# RP_ComputeModule3_rev_3_0_POWER.net
KiCad netlist of a schematic drawn in Altium Designer
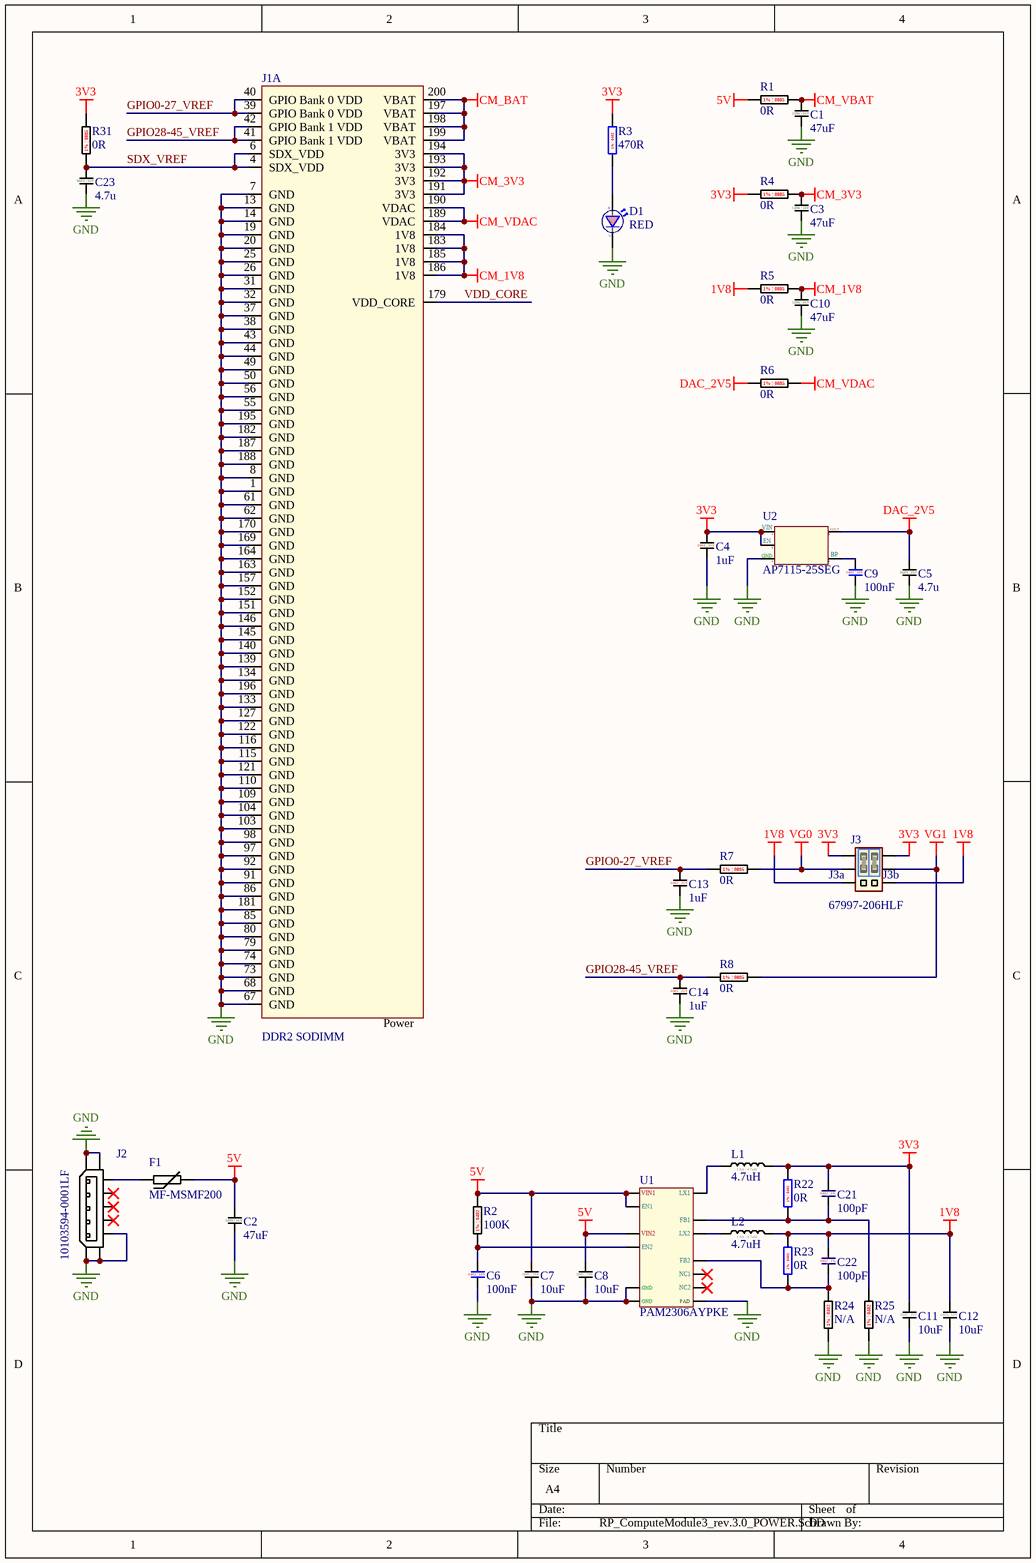
[diagram p0: RP_ComputeModule3_rev.3.0_POWER.SchDoc]

(export (version "E")
  (design (tool "Eeschema 10.0.6"))
  (components
    (comp (ref "C1")
      (value "47uF")
      (footprint "MURATA C1206 / CAPC3216X94N")
      (fields
        (field (name "MANUFACTURER") "TDK")
        (field (name "MANUFACTURER PART NUMBER") "C3216JB1C476M160AB")
        (field (name "TOLERANCE") "20%")
      )
      (libsource (lib "Murata_Capacitors") (part "C3216JB1C476M160AB"))
    )
    (comp (ref "C2")
      (value "47uF")
      (footprint "MURATA C1206 / CAPC3216X94N")
      (fields
        (field (name "MANUFACTURER") "TDK")
        (field (name "MANUFACTURER PART NUMBER") "C3216JB1C476M160AB")
        (field (name "TOLERANCE") "20%")
      )
      (libsource (lib "Murata_Capacitors") (part "C3216JB1C476M160AB"))
    )
    (comp (ref "C3")
      (value "47uF")
      (footprint "MURATA C1206 / CAPC3216X94N")
      (fields
        (field (name "MANUFACTURER") "TDK")
        (field (name "MANUFACTURER PART NUMBER") "C3216JB1C476M160AB")
        (field (name "TOLERANCE") "20%")
      )
      (libsource (lib "Murata_Capacitors") (part "C3216JB1C476M160AB"))
    )
    (comp (ref "C4")
      (value "1uF")
      (footprint "TDK 0402 C")
      (description "Multilayer Ceramic Capacitors MLCC - SMD/SMT 0402 25V 1uF X5R 10% T: 0.5mm")
      (fields
        (field (name "MANUFACTURER") "TDK")
        (field (name "MANUFACTURER PART NUMBER") "C1005X5R1E105K050BC")
      )
      (libsource (lib "TDK_Capacitors") (part "C1005X5R1E105K050BC"))
    )
    (comp (ref "C5")
      (value "4.7u")
      (footprint "0603 Murata")
      (description "4.7µF 35V Ceramic Capacitor X5R 0603 (1608 Metric) 0.063\" L x 0.031\" W (1.60mm x 0.80mm)")
      (fields
        (field (name "MANUFACTURER") "Murata")
        (field (name "MANUFACTURER PART NUMBER") "GRT188R6YA475KE13D")
      )
      (libsource (lib "Murata_Capacitors") (part "GRT188R6YA475KE13D"))
    )
    (comp (ref "C6")
      (value "100nF")
      (footprint "GJM 0402 C")
      (description "Multilayer Ceramic Capacitors MLCC - SMD/SMT 0402 0.1uF 10volts 5%")
      (fields
        (field (name "MANUFACTURER") "Murata Electronics")
        (field (name "MANUFACTURER PART NUMBER") "GRM155R71A104JA01D")
      )
      (libsource (lib "Murata_Capacitors") (part "GRM155R71A104JA01D"))
    )
    (comp (ref "C7")
      (value "10uF")
      (footprint "0805 CGA Series")
      (fields
        (field (name "MANUFACTURER") "TDK")
        (field (name "MANUFACTURER PART NUMBER") "C2012X7S1C106K125AC")
      )
      (libsource (lib "TDK_Capacitors") (part "C2012X7S1C106K125AC"))
    )
    (comp (ref "C8")
      (value "10uF")
      (footprint "0805 CGA Series")
      (fields
        (field (name "MANUFACTURER") "TDK")
        (field (name "MANUFACTURER PART NUMBER") "C2012X7S1C106K125AC")
      )
      (libsource (lib "TDK_Capacitors") (part "C2012X7S1C106K125AC"))
    )
    (comp (ref "C9")
      (value "100nF")
      (footprint "GJM 0402 C")
      (description "Multilayer Ceramic Capacitors MLCC - SMD/SMT 0402 0.1uF 10volts 5%")
      (fields
        (field (name "MANUFACTURER") "Murata Electronics")
        (field (name "MANUFACTURER PART NUMBER") "GRM155R71A104JA01D")
      )
      (libsource (lib "Murata_Capacitors") (part "GRM155R71A104JA01D"))
    )
    (comp (ref "C10")
      (value "47uF")
      (footprint "MURATA C1206 / CAPC3216X94N")
      (fields
        (field (name "MANUFACTURER") "TDK")
        (field (name "MANUFACTURER PART NUMBER") "C3216JB1C476M160AB")
        (field (name "TOLERANCE") "20%")
      )
      (libsource (lib "Murata_Capacitors") (part "C3216JB1C476M160AB"))
    )
    (comp (ref "C11")
      (value "10uF")
      (footprint "0805 CGA Series")
      (fields
        (field (name "MANUFACTURER") "TDK")
        (field (name "MANUFACTURER PART NUMBER") "C2012X7S1C106K125AC")
      )
      (libsource (lib "TDK_Capacitors") (part "C2012X7S1C106K125AC"))
    )
    (comp (ref "C12")
      (value "10uF")
      (footprint "0805 CGA Series")
      (fields
        (field (name "MANUFACTURER") "TDK")
        (field (name "MANUFACTURER PART NUMBER") "C2012X7S1C106K125AC")
      )
      (libsource (lib "TDK_Capacitors") (part "C2012X7S1C106K125AC"))
    )
    (comp (ref "C13")
      (value "1uF")
      (footprint "TDK 0402 C")
      (description "Multilayer Ceramic Capacitors MLCC - SMD/SMT 0402 25V 1uF X5R 10% T: 0.5mm")
      (fields
        (field (name "MANUFACTURER") "TDK")
        (field (name "MANUFACTURER PART NUMBER") "C1005X5R1E105K050BC")
      )
      (libsource (lib "TDK_Capacitors") (part "C1005X5R1E105K050BC"))
    )
    (comp (ref "C14")
      (value "1uF")
      (footprint "TDK 0402 C")
      (description "Multilayer Ceramic Capacitors MLCC - SMD/SMT 0402 25V 1uF X5R 10% T: 0.5mm")
      (fields
        (field (name "MANUFACTURER") "TDK")
        (field (name "MANUFACTURER PART NUMBER") "C1005X5R1E105K050BC")
      )
      (libsource (lib "TDK_Capacitors") (part "C1005X5R1E105K050BC"))
    )
    (comp (ref "C21")
      (value "100pF")
      (footprint "Cap0402 MIN Vishay N/A")
      (description "Multilayer Ceramic Capacitors MLCC - SMD/SMT 0402 100pF 50volts C0G 1%")
      (fields
        (field (name "MANUFACTURER") "Vishay Vitramon")
        (field (name "MANUFACTURER PART NUMBER") "VJ0402A101FXACW1BC")
      )
      (libsource (lib "Vishay_Library") (part "VJ0402A101FXACW1BC_NA"))
    )
    (comp (ref "C22")
      (value "100pF")
      (footprint "Cap0402 MIN Vishay N/A")
      (description "Multilayer Ceramic Capacitors MLCC - SMD/SMT 0402 100pF 50volts C0G 1%")
      (fields
        (field (name "MANUFACTURER") "Vishay Vitramon")
        (field (name "MANUFACTURER PART NUMBER") "VJ0402A101FXACW1BC")
      )
      (libsource (lib "Vishay_Library") (part "VJ0402A101FXACW1BC_NA"))
    )
    (comp (ref "C23")
      (value "4.7u")
      (footprint "0603 Murata")
      (description "4.7µF 35V Ceramic Capacitor X5R 0603 (1608 Metric) 0.063\" L x 0.031\" W (1.60mm x 0.80mm)")
      (fields
        (field (name "MANUFACTURER") "Murata")
        (field (name "MANUFACTURER PART NUMBER") "GRT188R6YA475KE13D")
      )
      (libsource (lib "Murata_Capacitors") (part "GRT188R6YA475KE13D"))
    )
    (comp (ref "D1")
      (value "RED")
      (footprint "ROHM 0603 LED")
      (description "LED RED DIFFUSED 0603 SMD")
      (fields (field (name "MANUFACTURER") "Rohm") (field (name "MANUFACTURER PART NUMBER") "SML-D12U8WT86"))
      (libsource (lib "Rohm_Library") (part "SML-D12U8WT86"))
    )
    (comp (ref "F1")
      (value "MF-MSMF200")
      (footprint "Bourns MF-MSMF (Style1)")
      (description "PTC RESETTABLE 2.00A 8V 1812")
      (fields (field (name "MANUFACTURER") "Bourns") (field (name "MANUFACTURER PART NUMBER") "MF-MSMF200-2"))
      (libsource (lib "Bourns_Library") (part "MF-MSMF200-2"))
    )
    (comp (ref "J1")
      (value "DDR2 SODIMM")
      (footprint "TE 1473005-4 (DDR2 SO-DIMM)")
      (description "TE CONNECTIVITY / AMP         1473005-4             SOCKET IC, DIMM, DDR2, 1.8V, 200WAY")
      (fields
        (field (name "MANUFACTURER") "TE Connectivity")
        (field (name "MANUFACTURER PART NUMBER") "1473005-4")
      )
      (libsource (lib "TEConnectivity_AMP") (part "1473005-4"))
    )
    (comp (ref "J2")
      (value "10103594-0001LF")
      (footprint "FCI_10103594-0001LF")
      (description "USB - micro B USB 2.0 Receptacle Connector 5 Position Surface Mount, Right Angle, Horizontal")
      (fields (field (name "MANUFACTURER") "Amphenol FCI"))
      (libsource (lib "Amphenol_Library") (part "10103594-0001LF"))
    )
    (comp (ref "J3")
      (value "67997-206HLF")
      (footprint "Amphenol 2x6 PINS 67997-206HLF")
      (description "6 Positions Header, Unshrouded Connector 0.100\" (2.54mm) Through Hole Gold or Gold, GXT™")
      (fields (field (name "MANUFACTURER") "Amphenol FCI"))
      (libsource (lib "Amphenol_Library") (part "67997-206HLF"))
    )
    (comp (ref "J3a")
      (value "Jumper")
      (footprint "Kobiconn 151-8011-E (Blue)")
      (description "Headers & Wire Housings MINI JUMPER GF 6.0MM CLOSE TYPE BLUE")
      (fields (field (name "MANUFACTURER") "Kobiconn") (field (name "MANUFACTURER PART NUMBER") "151-8011-E"))
      (libsource (lib "Kobiconn_Library") (part "151-8011-E"))
    )
    (comp (ref "J3b")
      (value "Jumper")
      (footprint "Kobiconn 151-8011-E (Blue)")
      (description "Headers & Wire Housings MINI JUMPER GF 6.0MM CLOSE TYPE BLUE")
      (fields (field (name "MANUFACTURER") "Kobiconn") (field (name "MANUFACTURER PART NUMBER") "151-8011-E"))
      (libsource (lib "Kobiconn_Library") (part "151-8011-E"))
    )
    (comp (ref "L1")
      (value "4.7uH")
      (footprint "Bourns SRN4018")
      (description "FIXED IND 4.7UH 1.9A 84 MOHM SMD")
      (fields (field (name "MANUFACTURER") "Bourns") (field (name "MANUFACTURER PART NUMBER") "SRN4018-4R7M"))
      (libsource (lib "Bourns_Library") (part "SRN4018-4R7M"))
    )
    (comp (ref "L2")
      (value "4.7uH")
      (footprint "Bourns SRN4018")
      (description "FIXED IND 4.7UH 1.9A 84 MOHM SMD")
      (fields (field (name "MANUFACTURER") "Bourns") (field (name "MANUFACTURER PART NUMBER") "SRN4018-4R7M"))
      (libsource (lib "Bourns_Library") (part "SRN4018-4R7M"))
    )
    (comp (ref "R1")
      (value "0R")
      (footprint "YAGEO RES0402")
      (description "Thick Film Resistors - SMD 1/8W 0.0ohm 1%")
      (fields
        (field (name "MANUFACTURER") "Yageo")
        (field (name "MANUFACTURER PART NUMBER") "AC0805FR-070RL")
      )
      (libsource (lib "YAGEO_Library") (part "AC0805FR-070RL"))
    )
    (comp (ref "R2")
      (value "100K")
      (footprint "RES0402")
      (description "Thick Film Resistors - SMD 0.125W 100Kohm 1% 200ppm")
      (fields
        (field (name "MANUFACTURER") "KOA Speer")
        (field (name "MANUFACTURER PART NUMBER") "SG73P1ETTP1003F")
      )
      (libsource (lib "KOA_Resistors") (part "SG73P1ETTP1003F"))
    )
    (comp (ref "R3")
      (value "470R")
      (footprint "Vishay RES0402")
      (description "RES SMD 470 OHM 1% 1/10W 0402")
      (fields
        (field (name "MANUFACTURER") "Vishay BCcomponents")
        (field (name "MANUFACTURER PART NUMBER") "MCS04020C4700FE000")
      )
      (libsource (lib "Vishay_Library") (part "MCS04020C4700FE000"))
    )
    (comp (ref "R4")
      (value "0R")
      (footprint "YAGEO RES0402")
      (description "Thick Film Resistors - SMD 1/8W 0.0ohm 1%")
      (fields
        (field (name "MANUFACTURER") "Yageo")
        (field (name "MANUFACTURER PART NUMBER") "AC0805FR-070RL")
      )
      (libsource (lib "YAGEO_Library") (part "AC0805FR-070RL"))
    )
    (comp (ref "R5")
      (value "0R")
      (footprint "YAGEO RES0402")
      (description "Thick Film Resistors - SMD 1/8W 0.0ohm 1%")
      (fields
        (field (name "MANUFACTURER") "Yageo")
        (field (name "MANUFACTURER PART NUMBER") "AC0805FR-070RL")
      )
      (libsource (lib "YAGEO_Library") (part "AC0805FR-070RL"))
    )
    (comp (ref "R6")
      (value "0R")
      (footprint "YAGEO RES0402")
      (description "Thick Film Resistors - SMD 1/8W 0.0ohm 1%")
      (fields
        (field (name "MANUFACTURER") "Yageo")
        (field (name "MANUFACTURER PART NUMBER") "AC0805FR-070RL")
      )
      (libsource (lib "YAGEO_Library") (part "AC0805FR-070RL"))
    )
    (comp (ref "R7")
      (value "0R")
      (footprint "YAGEO RES0402")
      (description "Thick Film Resistors - SMD 1/8W 0.0ohm 1%")
      (fields
        (field (name "MANUFACTURER") "Yageo")
        (field (name "MANUFACTURER PART NUMBER") "AC0805FR-070RL")
      )
      (libsource (lib "YAGEO_Library") (part "AC0805FR-070RL"))
    )
    (comp (ref "R8")
      (value "0R")
      (footprint "YAGEO RES0402")
      (description "Thick Film Resistors - SMD 1/8W 0.0ohm 1%")
      (fields
        (field (name "MANUFACTURER") "Yageo")
        (field (name "MANUFACTURER PART NUMBER") "AC0805FR-070RL")
      )
      (libsource (lib "YAGEO_Library") (part "AC0805FR-070RL"))
    )
    (comp (ref "R22")
      (value "0R")
      (footprint "Vishay Beyschlag MCS0402")
      (description "Res Thin Film 0402 0 Ohm Molded SMD Automotive Medical Paper T/R")
      (fields
        (field (name "MANUFACTURER") "Vishay Beyschlag")
        (field (name "MANUFACTURER PART NUMBER") "MCS04020Z0000ZE000")
      )
      (libsource (lib "Vishay_Library") (part "MCS04020Z0000ZE000"))
    )
    (comp (ref "R23")
      (value "0R")
      (footprint "Vishay Beyschlag MCS0402")
      (description "Res Thin Film 0402 0 Ohm Molded SMD Automotive Medical Paper T/R")
      (fields
        (field (name "MANUFACTURER") "Vishay Beyschlag")
        (field (name "MANUFACTURER PART NUMBER") "MCS04020Z0000ZE000")
      )
      (libsource (lib "Vishay_Library") (part "MCS04020Z0000ZE000"))
    )
    (comp (ref "R24")
      (value "N/A")
      (footprint "RES0402N/A")
      (libsource (lib "KOA_Resistors") (part "Resistor_N/A"))
    )
    (comp (ref "R25")
      (value "N/A")
      (footprint "RES0402N/A")
      (libsource (lib "KOA_Resistors") (part "Resistor_N/A"))
    )
    (comp (ref "R31")
      (value "0R")
      (footprint "YAGEO RES0402")
      (description "Thick Film Resistors - SMD 1/8W 0.0ohm 1%")
      (fields
        (field (name "MANUFACTURER") "Yageo")
        (field (name "MANUFACTURER PART NUMBER") "AC0805FR-070RL")
      )
      (libsource (lib "YAGEO_Library") (part "AC0805FR-070RL"))
    )
    (comp (ref "U1")
      (value "PAM2306AYPKE")
      (footprint "DIODES_SON45P300X300X80-13N")
      (description "Conv DC-DC Dual Step Down 2.5V 5.5V 12-Pin WDFN T/R")
      (fields (field (name "MANUFACTURER") "Diodes"))
      (libsource (lib "Diodes_Inc_Library") (part "PAM2306AYPKE"))
    )
    (comp (ref "U2")
      (value "AP7115-25SEG")
      (footprint "Diodes_SOT353_SC70-5_SOT65P210X110-5N")
      (description "IC REG LDO 2.5V 0.15A SOT353")
      (fields
        (field (name "MANUFACTURER") "Diodes")
        (field (name "MANUFACTURER PART NUMBER") "AP7115-25SEG-7")
      )
      (libsource (lib "Diodes_Inc_Library") (part "AP7115-25SEG-7"))
    )
  )
  (nets
    (net (code "1") (name "/GPIO0-27_VREF") (class "Default")
      (node (ref "C13") (pin "1") (pinfunction "1_1") (pintype "passive"))
      (node (ref "J1") (pin "39") (pinfunction "GPIO_Bank_0_VDD_39") (pintype "power_in"))
      (node (ref "J1") (pin "40") (pinfunction "GPIO_Bank_0_VDD_40") (pintype "power_in"))
      (node (ref "R7") (pin "2") (pinfunction "2_2") (pintype "passive"))
    )
    (net (code "2") (name "/GPIO28-45_VREF") (class "Default")
      (node (ref "C14") (pin "1") (pinfunction "1_1") (pintype "passive"))
      (node (ref "J1") (pin "41") (pinfunction "GPIO_Bank_1_VDD_41") (pintype "power_in"))
      (node (ref "J1") (pin "42") (pinfunction "GPIO_Bank_1_VDD_42") (pintype "power_in"))
      (node (ref "R8") (pin "2") (pinfunction "2_2") (pintype "passive"))
    )
    (net (code "3") (name "/SDX_VREF") (class "Default")
      (node (ref "C23") (pin "2") (pinfunction "2_2") (pintype "passive"))
      (node (ref "J1") (pin "4") (pinfunction "SDX_VDD_4") (pintype "power_in"))
      (node (ref "J1") (pin "6") (pinfunction "SDX_VDD_6") (pintype "power_in"))
      (node (ref "R31") (pin "2") (pinfunction "2_2") (pintype "passive"))
    )
    (net (code "4") (name "/VDD_CORE") (class "Default")
      (node (ref "J1") (pin "179") (pinfunction "VDD_CORE_179") (pintype "power_in"))
    )
    (net (code "5") (name "1V8") (class "Default")
      (node (ref "C12") (pin "1") (pinfunction "1_1") (pintype "passive"))
      (node (ref "C22") (pin "2") (pinfunction "2_2") (pintype "passive"))
      (node (ref "J3") (pin "5") (pinfunction "5_5") (pintype "passive"))
      (node (ref "J3") (pin "6") (pinfunction "6_6") (pintype "passive"))
      (node (ref "L2") (pin "2") (pinfunction "2_2") (pintype "passive"))
      (node (ref "R23") (pin "1") (pinfunction "1_1") (pintype "passive"))
      (node (ref "R5") (pin "2") (pinfunction "2_2") (pintype "passive"))
    )
    (net (code "6") (name "3V3") (class "Default")
      (node (ref "C11") (pin "1") (pinfunction "1_1") (pintype "passive"))
      (node (ref "C21") (pin "2") (pinfunction "2_2") (pintype "passive"))
      (node (ref "C4") (pin "1") (pinfunction "1_1") (pintype "passive"))
      (node (ref "J3") (pin "1") (pinfunction "1_1") (pintype "passive"))
      (node (ref "J3") (pin "2") (pinfunction "2_2") (pintype "passive"))
      (node (ref "L1") (pin "2") (pinfunction "2_2") (pintype "passive"))
      (node (ref "R22") (pin "1") (pinfunction "1_1") (pintype "passive"))
      (node (ref "R3") (pin "1") (pinfunction "1_1") (pintype "passive"))
      (node (ref "R31") (pin "1") (pinfunction "1_1") (pintype "passive"))
      (node (ref "R4") (pin "2") (pinfunction "2_2") (pintype "passive"))
      (node (ref "U2") (pin "1") (pinfunction "1_1") (pintype "passive"))
      (node (ref "U2") (pin "3") (pinfunction "3_3") (pintype "passive"))
    )
    (net (code "7") (name "5V") (class "Default")
      (node (ref "C2") (pin "2") (pinfunction "2_2") (pintype "passive"))
      (node (ref "C7") (pin "1") (pinfunction "1_1") (pintype "passive"))
      (node (ref "C8") (pin "1") (pinfunction "1_1") (pintype "passive"))
      (node (ref "F1") (pin "2") (pinfunction "2_2") (pintype "passive"))
      (node (ref "R1") (pin "2") (pinfunction "2_2") (pintype "passive"))
      (node (ref "R2") (pin "1") (pinfunction "1_1") (pintype "passive"))
      (node (ref "U1") (pin "1") (pinfunction "1_1") (pintype "passive"))
      (node (ref "U1") (pin "6") (pinfunction "6_6") (pintype "passive"))
      (node (ref "U1") (pin "7") (pinfunction "7_7") (pintype "passive"))
    )
    (net (code "8") (name "CM_1V8") (class "Default")
      (node (ref "C10") (pin "2") (pinfunction "2_2") (pintype "passive"))
      (node (ref "J1") (pin "183") (pinfunction "1V8_183") (pintype "power_in"))
      (node (ref "J1") (pin "184") (pinfunction "1V8_184") (pintype "power_in"))
      (node (ref "J1") (pin "185") (pinfunction "1V8_185") (pintype "power_in"))
      (node (ref "J1") (pin "186") (pinfunction "1V8_186") (pintype "power_in"))
      (node (ref "R5") (pin "1") (pinfunction "1_1") (pintype "passive"))
    )
    (net (code "9") (name "CM_3V3") (class "Default")
      (node (ref "C3") (pin "2") (pinfunction "2_2") (pintype "passive"))
      (node (ref "J1") (pin "191") (pinfunction "3V3_191") (pintype "power_in"))
      (node (ref "J1") (pin "192") (pinfunction "3V3_192") (pintype "power_in"))
      (node (ref "J1") (pin "193") (pinfunction "3V3_193") (pintype "power_in"))
      (node (ref "J1") (pin "194") (pinfunction "3V3_194") (pintype "power_in"))
      (node (ref "R4") (pin "1") (pinfunction "1_1") (pintype "passive"))
    )
    (net (code "10") (name "CM_BAT") (class "Default")
      (node (ref "J1") (pin "197") (pinfunction "VBAT_197") (pintype "power_in"))
      (node (ref "J1") (pin "198") (pinfunction "VBAT_198") (pintype "power_in"))
      (node (ref "J1") (pin "199") (pinfunction "VBAT_199") (pintype "power_in"))
      (node (ref "J1") (pin "200") (pinfunction "VBAT_200") (pintype "power_in"))
    )
    (net (code "11") (name "CM_VBAT") (class "Default")
      (node (ref "C1") (pin "2") (pinfunction "2_2") (pintype "passive"))
      (node (ref "R1") (pin "1") (pinfunction "1_1") (pintype "passive"))
    )
    (net (code "12") (name "CM_VDAC") (class "Default")
      (node (ref "J1") (pin "189") (pinfunction "VDAC_189") (pintype "power_in"))
      (node (ref "J1") (pin "190") (pinfunction "VDAC_190") (pintype "power_in"))
      (node (ref "R6") (pin "1") (pinfunction "1_1") (pintype "passive"))
    )
    (net (code "13") (name "DAC_2V5") (class "Default")
      (node (ref "C5") (pin "2") (pinfunction "2_2") (pintype "passive"))
      (node (ref "R6") (pin "2") (pinfunction "2_2") (pintype "passive"))
      (node (ref "U2") (pin "5") (pinfunction "5_5") (pintype "passive"))
    )
    (net (code "14") (name "GND") (class "Default")
      (node (ref "C1") (pin "1") (pinfunction "1_1") (pintype "passive"))
      (node (ref "C10") (pin "1") (pinfunction "1_1") (pintype "passive"))
      (node (ref "C11") (pin "2") (pinfunction "2_2") (pintype "passive"))
      (node (ref "C12") (pin "2") (pinfunction "2_2") (pintype "passive"))
      (node (ref "C13") (pin "2") (pinfunction "2_2") (pintype "passive"))
      (node (ref "C14") (pin "2") (pinfunction "2_2") (pintype "passive"))
      (node (ref "C2") (pin "1") (pinfunction "1_1") (pintype "passive"))
      (node (ref "C23") (pin "1") (pinfunction "1_1") (pintype "passive"))
      (node (ref "C3") (pin "1") (pinfunction "1_1") (pintype "passive"))
      (node (ref "C4") (pin "2") (pinfunction "2_2") (pintype "passive"))
      (node (ref "C5") (pin "1") (pinfunction "1_1") (pintype "passive"))
      (node (ref "C6") (pin "1") (pinfunction "1_1") (pintype "passive"))
      (node (ref "C7") (pin "2") (pinfunction "2_2") (pintype "passive"))
      (node (ref "C8") (pin "2") (pinfunction "2_2") (pintype "passive"))
      (node (ref "C9") (pin "1") (pinfunction "1_1") (pintype "passive"))
      (node (ref "D1") (pin "C") (pinfunction "C_C") (pintype "passive"))
      (node (ref "J1") (pin "1") (pinfunction "GND_1") (pintype "power_in"))
      (node (ref "J1") (pin "103") (pinfunction "GND_103") (pintype "power_in"))
      (node (ref "J1") (pin "104") (pinfunction "GND_104") (pintype "power_in"))
      (node (ref "J1") (pin "109") (pinfunction "GND_109") (pintype "power_in"))
      (node (ref "J1") (pin "110") (pinfunction "GND_110") (pintype "power_in"))
      (node (ref "J1") (pin "115") (pinfunction "GND_115") (pintype "power_in"))
      (node (ref "J1") (pin "116") (pinfunction "GND_116") (pintype "power_in"))
      (node (ref "J1") (pin "121") (pinfunction "GND_121") (pintype "power_in"))
      (node (ref "J1") (pin "122") (pinfunction "GND_122") (pintype "power_in"))
      (node (ref "J1") (pin "127") (pinfunction "GND_127") (pintype "power_in"))
      (node (ref "J1") (pin "13") (pinfunction "GND_13") (pintype "power_in"))
      (node (ref "J1") (pin "133") (pinfunction "GND_133") (pintype "power_in"))
      (node (ref "J1") (pin "134") (pinfunction "GND_134") (pintype "power_in"))
      (node (ref "J1") (pin "139") (pinfunction "GND_139") (pintype "power_in"))
      (node (ref "J1") (pin "14") (pinfunction "GND_14") (pintype "power_in"))
      (node (ref "J1") (pin "140") (pinfunction "GND_140") (pintype "power_in"))
      (node (ref "J1") (pin "145") (pinfunction "GND_145") (pintype "power_in"))
      (node (ref "J1") (pin "146") (pinfunction "GND_146") (pintype "power_in"))
      (node (ref "J1") (pin "151") (pinfunction "GND_151") (pintype "power_in"))
      (node (ref "J1") (pin "152") (pinfunction "GND_152") (pintype "power_in"))
      (node (ref "J1") (pin "157") (pinfunction "GND_157") (pintype "power_in"))
      (node (ref "J1") (pin "163") (pinfunction "GND_163") (pintype "power_in"))
      (node (ref "J1") (pin "164") (pinfunction "GND_164") (pintype "power_in"))
      (node (ref "J1") (pin "169") (pinfunction "GND_169") (pintype "power_in"))
      (node (ref "J1") (pin "170") (pinfunction "GND_170") (pintype "power_in"))
      (node (ref "J1") (pin "181") (pinfunction "GND_181") (pintype "power_in"))
      (node (ref "J1") (pin "182") (pinfunction "GND_182") (pintype "power_in"))
      (node (ref "J1") (pin "187") (pinfunction "GND_187") (pintype "power_in"))
      (node (ref "J1") (pin "188") (pinfunction "GND_188") (pintype "power_in"))
      (node (ref "J1") (pin "19") (pinfunction "GND_19") (pintype "power_in"))
      (node (ref "J1") (pin "195") (pinfunction "GND_195") (pintype "power_in"))
      (node (ref "J1") (pin "196") (pinfunction "GND_196") (pintype "power_in"))
      (node (ref "J1") (pin "20") (pinfunction "GND_20") (pintype "power_in"))
      (node (ref "J1") (pin "25") (pinfunction "GND_25") (pintype "power_in"))
      (node (ref "J1") (pin "26") (pinfunction "GND_26") (pintype "power_in"))
      (node (ref "J1") (pin "31") (pinfunction "GND_31") (pintype "power_in"))
      (node (ref "J1") (pin "32") (pinfunction "GND_32") (pintype "power_in"))
      (node (ref "J1") (pin "37") (pinfunction "GND_37") (pintype "power_in"))
      (node (ref "J1") (pin "38") (pinfunction "GND_38") (pintype "power_in"))
      (node (ref "J1") (pin "43") (pinfunction "GND_43") (pintype "power_in"))
      (node (ref "J1") (pin "44") (pinfunction "GND_44") (pintype "power_in"))
      (node (ref "J1") (pin "49") (pinfunction "GND_49") (pintype "power_in"))
      (node (ref "J1") (pin "50") (pinfunction "GND_50") (pintype "power_in"))
      (node (ref "J1") (pin "55") (pinfunction "GND_55") (pintype "power_in"))
      (node (ref "J1") (pin "56") (pinfunction "GND_56") (pintype "power_in"))
      (node (ref "J1") (pin "61") (pinfunction "GND_61") (pintype "power_in"))
      (node (ref "J1") (pin "62") (pinfunction "GND_62") (pintype "power_in"))
      (node (ref "J1") (pin "67") (pinfunction "GND_67") (pintype "power_in"))
      (node (ref "J1") (pin "68") (pinfunction "GND_68") (pintype "power_in"))
      (node (ref "J1") (pin "7") (pinfunction "GND_7") (pintype "power_in"))
      (node (ref "J1") (pin "73") (pinfunction "GND_73") (pintype "power_in"))
      (node (ref "J1") (pin "74") (pinfunction "GND_74") (pintype "power_in"))
      (node (ref "J1") (pin "79") (pinfunction "GND_79") (pintype "power_in"))
      (node (ref "J1") (pin "8") (pinfunction "GND_8") (pintype "power_in"))
      (node (ref "J1") (pin "80") (pinfunction "GND_80") (pintype "power_in"))
      (node (ref "J1") (pin "85") (pinfunction "GND_85") (pintype "power_in"))
      (node (ref "J1") (pin "86") (pinfunction "GND_86") (pintype "power_in"))
      (node (ref "J1") (pin "91") (pinfunction "GND_91") (pintype "power_in"))
      (node (ref "J1") (pin "92") (pinfunction "GND_92") (pintype "power_in"))
      (node (ref "J1") (pin "97") (pinfunction "GND_97") (pintype "power_in"))
      (node (ref "J1") (pin "98") (pinfunction "GND_98") (pintype "power_in"))
      (node (ref "J2") (pin "10") (pinfunction "10_10") (pintype "passive"))
      (node (ref "J2") (pin "11") (pinfunction "11_11") (pintype "passive"))
      (node (ref "J2") (pin "5") (pinfunction "5_5") (pintype "passive"))
      (node (ref "J2") (pin "6") (pinfunction "6_6") (pintype "passive"))
      (node (ref "J2") (pin "7") (pinfunction "7_7") (pintype "passive"))
      (node (ref "J2") (pin "8") (pinfunction "8_8") (pintype "passive"))
      (node (ref "J2") (pin "9") (pinfunction "9_9") (pintype "passive"))
      (node (ref "R24") (pin "2") (pinfunction "2_2") (pintype "passive"))
      (node (ref "R25") (pin "2") (pinfunction "2_2") (pintype "passive"))
      (node (ref "U1") (pin "13") (pinfunction "13_13") (pintype "passive"))
      (node (ref "U1") (pin "3") (pinfunction "3_3") (pintype "passive"))
      (node (ref "U1") (pin "9") (pinfunction "9_9") (pintype "passive"))
      (node (ref "U2") (pin "2") (pinfunction "2_2") (pintype "passive"))
    )
    (net (code "15") (name "Net-(C6-Pad2)") (class "Default")
      (node (ref "C6") (pin "2") (pinfunction "2_2") (pintype "passive"))
      (node (ref "R2") (pin "2") (pinfunction "2_2") (pintype "passive"))
      (node (ref "U1") (pin "12") (pinfunction "12_12") (pintype "passive"))
    )
    (net (code "16") (name "Net-(C9-Pad2)") (class "Default")
      (node (ref "C9") (pin "2") (pinfunction "2_2") (pintype "passive"))
      (node (ref "U2") (pin "4") (pinfunction "4_4") (pintype "passive"))
    )
    (net (code "17") (name "Net-(C21-Pad1)") (class "Default")
      (node (ref "C21") (pin "1") (pinfunction "1_1") (pintype "passive"))
      (node (ref "R22") (pin "2") (pinfunction "2_2") (pintype "passive"))
      (node (ref "R25") (pin "1") (pinfunction "1_1") (pintype "passive"))
      (node (ref "U1") (pin "4") (pinfunction "4_4") (pintype "passive"))
    )
    (net (code "18") (name "Net-(C22-Pad1)") (class "Default")
      (node (ref "C22") (pin "1") (pinfunction "1_1") (pintype "passive"))
      (node (ref "R23") (pin "2") (pinfunction "2_2") (pintype "passive"))
      (node (ref "R24") (pin "1") (pinfunction "1_1") (pintype "passive"))
      (node (ref "U1") (pin "10") (pinfunction "10_10") (pintype "passive"))
    )
    (net (code "19") (name "Net-(D1-PadA)") (class "Default")
      (node (ref "D1") (pin "A") (pinfunction "A_A") (pintype "passive"))
      (node (ref "R3") (pin "2") (pinfunction "2_2") (pintype "passive"))
    )
    (net (code "20") (name "Net-(F1-Pad1)") (class "Default")
      (node (ref "F1") (pin "1") (pinfunction "1_1") (pintype "passive"))
      (node (ref "J2") (pin "1") (pinfunction "1_1") (pintype "passive"))
    )
    (net (code "21") (name "Net-(L1-Pad1)") (class "Default")
      (node (ref "L1") (pin "1") (pinfunction "1_1") (pintype "passive"))
      (node (ref "U1") (pin "8") (pinfunction "8_8") (pintype "passive"))
    )
    (net (code "22") (name "Net-(L2-Pad1)") (class "Default")
      (node (ref "L2") (pin "1") (pinfunction "1_1") (pintype "passive"))
      (node (ref "U1") (pin "2") (pinfunction "2_2") (pintype "passive"))
    )
    (net (code "23") (name "VG0") (class "Default")
      (node (ref "J3") (pin "3") (pinfunction "3_3") (pintype "passive"))
      (node (ref "R7") (pin "1") (pinfunction "1_1") (pintype "passive"))
    )
    (net (code "24") (name "VG1") (class "Default")
      (node (ref "J3") (pin "4") (pinfunction "4_4") (pintype "passive"))
      (node (ref "R8") (pin "1") (pinfunction "1_1") (pintype "passive"))
    )
    (net (code "25") (name "unconnected-(J2-Pad2)") (class "Default")
      (node (ref "J2") (pin "2") (pinfunction "2_2") (pintype "passive+no_connect"))
    )
    (net (code "26") (name "unconnected-(J2-Pad3)") (class "Default")
      (node (ref "J2") (pin "3") (pinfunction "3_3") (pintype "passive+no_connect"))
    )
    (net (code "27") (name "unconnected-(J2-Pad4)") (class "Default")
      (node (ref "J2") (pin "4") (pinfunction "4_4") (pintype "passive+no_connect"))
    )
    (net (code "28") (name "unconnected-(U1-Pad5)") (class "Default")
      (node (ref "U1") (pin "5") (pinfunction "5_5") (pintype "passive+no_connect"))
    )
    (net (code "29") (name "unconnected-(U1-Pad11)") (class "Default")
      (node (ref "U1") (pin "11") (pinfunction "11_11") (pintype "passive+no_connect"))
    )
  )
)
